# led_analog_watch_mvmt_v1_2.net
KiCad netlist of a schematic drawn in EAGLE
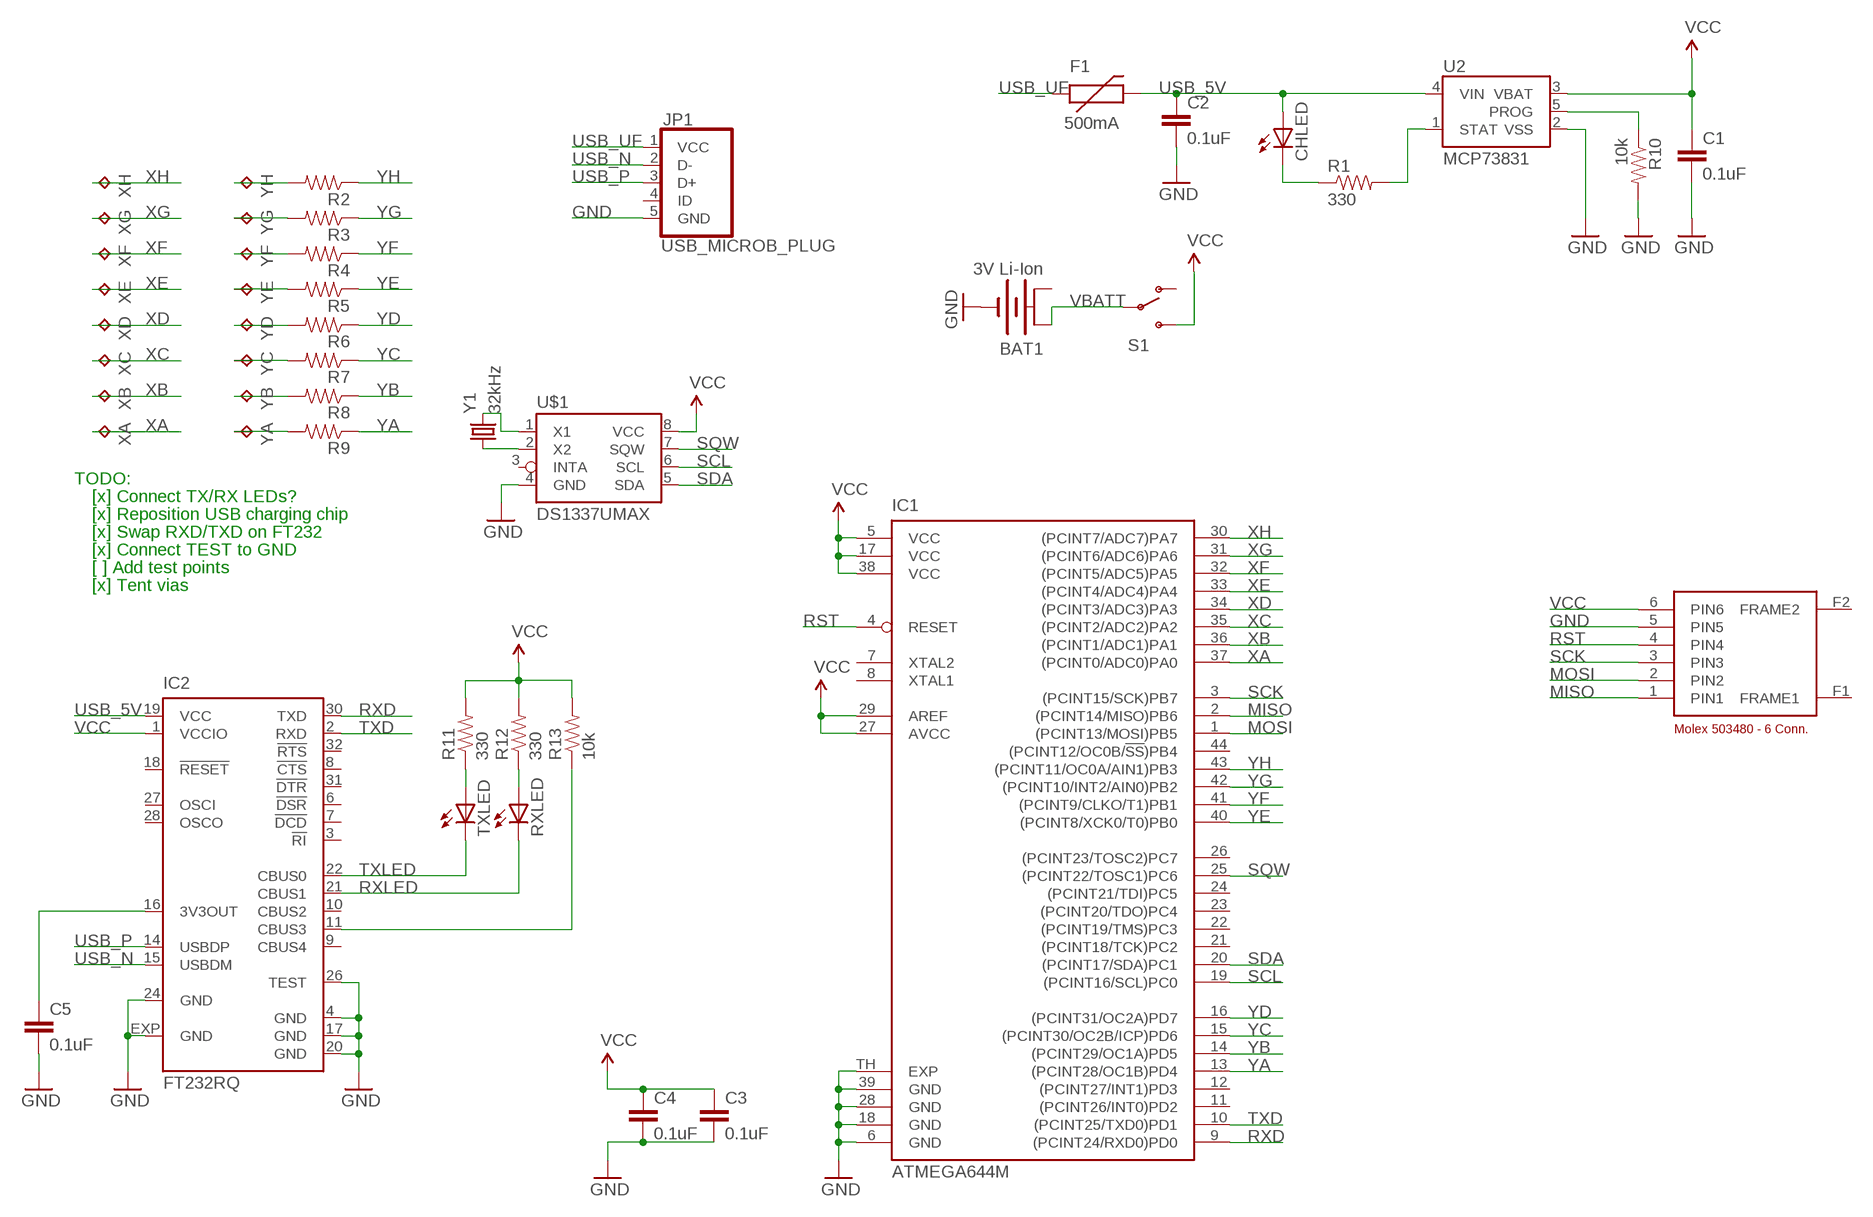
[diagram p0: schematic, sheet 1]

(export (version "E")
  (design (tool "Eeschema 10.0.6"))
  (components
    (comp (ref "BAT1")
      (value "3V Li-Ion")
      (footprint "eagle-import:BATTCON_245MM_PTH")
      (libsource (lib "eagle-import") (part "BATTERY245PTH"))
    )
    (comp (ref "C1")
      (value "0.1uF")
      (footprint "eagle-import:0603-CAP")
      (libsource (lib "eagle-import") (part "CAP-0603"))
    )
    (comp (ref "C2")
      (value "0.1uF")
      (footprint "eagle-import:0603-CAP")
      (libsource (lib "eagle-import") (part "CAP-0603"))
    )
    (comp (ref "C3")
      (value "0.1uF")
      (footprint "eagle-import:0603-CAP")
      (libsource (lib "eagle-import") (part "CAP-0603"))
    )
    (comp (ref "C4")
      (value "0.1uF")
      (footprint "eagle-import:0603-CAP")
      (libsource (lib "eagle-import") (part "CAP-0603"))
    )
    (comp (ref "C5")
      (value "0.1uF")
      (footprint "eagle-import:0603-CAP")
      (libsource (lib "eagle-import") (part "CAP-0603"))
    )
    (comp (ref "CHLED")
      (value "LED-0402")
      (footprint "eagle-import:0402")
      (libsource (lib "eagle-import") (part "LED-0402"))
    )
    (comp (ref "F1")
      (value "500mA")
      (footprint "eagle-import:0603")
      (libsource (lib "eagle-import") (part "PTC0603"))
    )
    (comp (ref "IC1")
      (value "ATMEGA644M")
      (footprint "eagle-import:MLF44-TH")
      (fields (field (name "MPN") "ATMEGA644P-20MU"))
      (libsource (lib "eagle-import") (part "ATMEGA644M"))
    )
    (comp (ref "IC2")
      (value "FT232RQ")
      (footprint "eagle-import:QFN32")
      (libsource (lib "eagle-import") (part "FT232RQ"))
    )
    (comp (ref "JP1")
      (value "USB_MICROB_PLUG")
      (footprint "eagle-import:USB_MICRO_B_TYCO")
      (libsource (lib "eagle-import") (part "USB_MICROB_PLUG"))
    )
    (comp (ref "R1")
      (value "330")
      (footprint "eagle-import:0603")
      (libsource (lib "eagle-import") (part "RESISTOR-0603"))
    )
    (comp (ref "R2")
      (value "RESISTOR-0603")
      (footprint "eagle-import:0603")
      (libsource (lib "eagle-import") (part "RESISTOR-0603"))
    )
    (comp (ref "R3")
      (value "RESISTOR-0603")
      (footprint "eagle-import:0603")
      (libsource (lib "eagle-import") (part "RESISTOR-0603"))
    )
    (comp (ref "R4")
      (value "RESISTOR-0603")
      (footprint "eagle-import:0603")
      (libsource (lib "eagle-import") (part "RESISTOR-0603"))
    )
    (comp (ref "R5")
      (value "RESISTOR-0603")
      (footprint "eagle-import:0603")
      (libsource (lib "eagle-import") (part "RESISTOR-0603"))
    )
    (comp (ref "R6")
      (value "RESISTOR-0603")
      (footprint "eagle-import:0603")
      (libsource (lib "eagle-import") (part "RESISTOR-0603"))
    )
    (comp (ref "R7")
      (value "RESISTOR-0603")
      (footprint "eagle-import:0603")
      (libsource (lib "eagle-import") (part "RESISTOR-0603"))
    )
    (comp (ref "R8")
      (value "RESISTOR-0603")
      (footprint "eagle-import:0603")
      (libsource (lib "eagle-import") (part "RESISTOR-0603"))
    )
    (comp (ref "R9")
      (value "RESISTOR-0603")
      (footprint "eagle-import:0603")
      (libsource (lib "eagle-import") (part "RESISTOR-0603"))
    )
    (comp (ref "R10")
      (value "10k")
      (footprint "eagle-import:0603")
      (libsource (lib "eagle-import") (part "RESISTOR-0603"))
    )
    (comp (ref "R11")
      (value "330")
      (footprint "eagle-import:0603")
      (libsource (lib "eagle-import") (part "RESISTOR-0603"))
    )
    (comp (ref "R12")
      (value "330")
      (footprint "eagle-import:0603")
      (libsource (lib "eagle-import") (part "RESISTOR-0603"))
    )
    (comp (ref "R13")
      (value "10k")
      (footprint "eagle-import:0603")
      (libsource (lib "eagle-import") (part "RESISTOR-0603"))
    )
    (comp (ref "RXLED")
      (value "LED-0402")
      (footprint "eagle-import:0402")
      (libsource (lib "eagle-import") (part "LED-0402"))
    )
    (comp (ref "S1")
      (value "SWITCH-SPSTMA12R")
      (footprint "eagle-import:SWITCH-MA12R")
      (libsource (lib "eagle-import") (part "SWITCH-SPSTMA12R"))
    )
    (comp (ref "TXLED")
      (value "LED-0402")
      (footprint "eagle-import:0402")
      (libsource (lib "eagle-import") (part "LED-0402"))
    )
    (comp (ref "U$1")
      (value "DS1337UMAX")
      (footprint "eagle-import:UMAX8")
      (libsource (lib "eagle-import") (part "DS1337UMAX"))
    )
    (comp (ref "U$2")
      (value "MOLEX_503480")
      (footprint "eagle-import:MOLEX_503480")
      (libsource (lib "eagle-import") (part "MOLEX_503480"))
    )
    (comp (ref "U2")
      (value "MCP73831")
      (footprint "eagle-import:SOT23-5")
      (libsource (lib "eagle-import") (part "MCP73831"))
    )
    (comp (ref "XA")
      (value "TPTP20R")
      (footprint "eagle-import:TP20R")
      (libsource (lib "eagle-import") (part "TPTP20R"))
    )
    (comp (ref "XB")
      (value "TPTP20R")
      (footprint "eagle-import:TP20R")
      (libsource (lib "eagle-import") (part "TPTP20R"))
    )
    (comp (ref "XC")
      (value "TPTP20R")
      (footprint "eagle-import:TP20R")
      (libsource (lib "eagle-import") (part "TPTP20R"))
    )
    (comp (ref "XD")
      (value "TPTP20R")
      (footprint "eagle-import:TP20R")
      (libsource (lib "eagle-import") (part "TPTP20R"))
    )
    (comp (ref "XE")
      (value "TPTP20R")
      (footprint "eagle-import:TP20R")
      (libsource (lib "eagle-import") (part "TPTP20R"))
    )
    (comp (ref "XF")
      (value "TPTP20R")
      (footprint "eagle-import:TP20R")
      (libsource (lib "eagle-import") (part "TPTP20R"))
    )
    (comp (ref "XG")
      (value "TPTP20R")
      (footprint "eagle-import:TP20R")
      (libsource (lib "eagle-import") (part "TPTP20R"))
    )
    (comp (ref "XH")
      (value "TPTP20R")
      (footprint "eagle-import:TP20R")
      (libsource (lib "eagle-import") (part "TPTP20R"))
    )
    (comp (ref "Y1")
      (value "32kHz")
      (footprint "eagle-import:CRYSTAL-ABS10-SMD")
      (libsource (lib "eagle-import") (part "CRYSTALABS10"))
    )
    (comp (ref "YA")
      (value "TPTP20R")
      (footprint "eagle-import:TP20R")
      (libsource (lib "eagle-import") (part "TPTP20R"))
    )
    (comp (ref "YB")
      (value "TPTP20R")
      (footprint "eagle-import:TP20R")
      (libsource (lib "eagle-import") (part "TPTP20R"))
    )
    (comp (ref "YC")
      (value "TPTP20R")
      (footprint "eagle-import:TP20R")
      (libsource (lib "eagle-import") (part "TPTP20R"))
    )
    (comp (ref "YD")
      (value "TPTP20R")
      (footprint "eagle-import:TP20R")
      (libsource (lib "eagle-import") (part "TPTP20R"))
    )
    (comp (ref "YE")
      (value "TPTP20R")
      (footprint "eagle-import:TP20R")
      (libsource (lib "eagle-import") (part "TPTP20R"))
    )
    (comp (ref "YF")
      (value "TPTP20R")
      (footprint "eagle-import:TP20R")
      (libsource (lib "eagle-import") (part "TPTP20R"))
    )
    (comp (ref "YG")
      (value "TPTP20R")
      (footprint "eagle-import:TP20R")
      (libsource (lib "eagle-import") (part "TPTP20R"))
    )
    (comp (ref "YH")
      (value "TPTP20R")
      (footprint "eagle-import:TP20R")
      (libsource (lib "eagle-import") (part "TPTP20R"))
    )
  )
  (nets
    (net (code "1") (name "/+B") (class "Default")
      (node (ref "BAT1") (pin "1") (pinfunction "+B_1") (pintype "power_in"))
    )
    (net (code "2") (name "/MISO") (class "Default")
      (node (ref "IC1") (pin "2") (pinfunction "(PCINT14/MISO)PB6_2") (pintype "bidirectional"))
      (node (ref "U$2") (pin "1") (pinfunction "PIN1_1") (pintype "bidirectional"))
    )
    (net (code "3") (name "/MOSI") (class "Default")
      (node (ref "IC1") (pin "1") (pinfunction "(PCINT13/MOSI)PB5_1") (pintype "bidirectional"))
      (node (ref "U$2") (pin "2") (pinfunction "PIN2_2") (pintype "bidirectional"))
    )
    (net (code "4") (name "/RST") (class "Default")
      (node (ref "IC1") (pin "4") (pinfunction "RESET_4") (pintype "input"))
      (node (ref "U$2") (pin "4") (pinfunction "PIN4_4") (pintype "bidirectional"))
    )
    (net (code "5") (name "/RXD") (class "Default")
      (node (ref "IC1") (pin "9") (pinfunction "(PCINT24/RXD0)PD0_9") (pintype "bidirectional"))
      (node (ref "IC2") (pin "30") (pinfunction "TXD_30") (pintype "output"))
    )
    (net (code "6") (name "/RXLED") (class "Default")
      (node (ref "IC2") (pin "21") (pinfunction "CBUS1_21") (pintype "bidirectional"))
      (node (ref "RXLED") (pin "2") (pinfunction "C_2") (pintype "passive"))
    )
    (net (code "7") (name "/SCK") (class "Default")
      (node (ref "IC1") (pin "3") (pinfunction "(PCINT15/SCK)PB7_3") (pintype "bidirectional"))
      (node (ref "U$2") (pin "3") (pinfunction "PIN3_3") (pintype "bidirectional"))
    )
    (net (code "8") (name "/SCL") (class "Default")
      (node (ref "IC1") (pin "19") (pinfunction "(PCINT16/SCL)PC0_19") (pintype "output"))
      (node (ref "U$1") (pin "6") (pinfunction "SCL_6") (pintype "bidirectional"))
    )
    (net (code "9") (name "/SDA") (class "Default")
      (node (ref "IC1") (pin "20") (pinfunction "(PCINT17/SDA)PC1_20") (pintype "output"))
      (node (ref "U$1") (pin "5") (pinfunction "SDA_5") (pintype "bidirectional"))
    )
    (net (code "10") (name "/SQW") (class "Default")
      (node (ref "IC1") (pin "25") (pinfunction "(PCINT22/TOSC1)PC6_25") (pintype "output"))
      (node (ref "U$1") (pin "7") (pinfunction "SQW_7") (pintype "bidirectional"))
    )
    (net (code "11") (name "/TXD") (class "Default")
      (node (ref "IC1") (pin "10") (pinfunction "(PCINT25/TXD0)PD1_10") (pintype "bidirectional"))
      (node (ref "IC2") (pin "2") (pinfunction "RXD_2") (pintype "input"))
    )
    (net (code "12") (name "/TXLED") (class "Default")
      (node (ref "IC2") (pin "22") (pinfunction "CBUS0_22") (pintype "bidirectional"))
      (node (ref "TXLED") (pin "2") (pinfunction "C_2") (pintype "passive"))
    )
    (net (code "13") (name "/USB_5V") (class "Default")
      (node (ref "C2") (pin "1") (pinfunction "1_1") (pintype "passive"))
      (node (ref "CHLED") (pin "1") (pinfunction "A_1") (pintype "passive"))
      (node (ref "F1") (pin "2") (pinfunction "2_2") (pintype "bidirectional"))
      (node (ref "IC2") (pin "19") (pinfunction "VCC_19") (pintype "power_in"))
      (node (ref "U2") (pin "4") (pinfunction "VIN_4") (pintype "power_in"))
    )
    (net (code "14") (name "/USB_N") (class "Default")
      (node (ref "IC2") (pin "15") (pinfunction "USBDM_15") (pintype "bidirectional"))
      (node (ref "JP1") (pin "2") (pinfunction "D-_2") (pintype "bidirectional"))
    )
    (net (code "15") (name "/USB_P") (class "Default")
      (node (ref "IC2") (pin "14") (pinfunction "USBDP_14") (pintype "bidirectional"))
      (node (ref "JP1") (pin "3") (pinfunction "D+_3") (pintype "bidirectional"))
    )
    (net (code "16") (name "/USB_UF") (class "Default")
      (node (ref "F1") (pin "1") (pinfunction "1_1") (pintype "bidirectional"))
      (node (ref "JP1") (pin "1") (pinfunction "VCC_1") (pintype "bidirectional"))
    )
    (net (code "17") (name "/VBATT") (class "Default")
      (node (ref "BAT1") (pin "3") (pinfunction "+A_3") (pintype "power_in"))
      (node (ref "S1") (pin "2") (pinfunction "P_2") (pintype "passive"))
    )
    (net (code "18") (name "/XA") (class "Default")
      (node (ref "IC1") (pin "37") (pinfunction "(PCINT0/ADC0)PA0_37") (pintype "bidirectional"))
      (node (ref "XA") (pin "TP") (pinfunction "TP_TP") (pintype "input"))
    )
    (net (code "19") (name "/XB") (class "Default")
      (node (ref "IC1") (pin "36") (pinfunction "(PCINT1/ADC1)PA1_36") (pintype "bidirectional"))
      (node (ref "XB") (pin "TP") (pinfunction "TP_TP") (pintype "input"))
    )
    (net (code "20") (name "/XC") (class "Default")
      (node (ref "IC1") (pin "35") (pinfunction "(PCINT2/ADC2)PA2_35") (pintype "bidirectional"))
      (node (ref "XC") (pin "TP") (pinfunction "TP_TP") (pintype "input"))
    )
    (net (code "21") (name "/XD") (class "Default")
      (node (ref "IC1") (pin "34") (pinfunction "(PCINT3/ADC3)PA3_34") (pintype "bidirectional"))
      (node (ref "XD") (pin "TP") (pinfunction "TP_TP") (pintype "input"))
    )
    (net (code "22") (name "/XE") (class "Default")
      (node (ref "IC1") (pin "33") (pinfunction "(PCINT4/ADC4)PA4_33") (pintype "bidirectional"))
      (node (ref "XE") (pin "TP") (pinfunction "TP_TP") (pintype "input"))
    )
    (net (code "23") (name "/XF") (class "Default")
      (node (ref "IC1") (pin "32") (pinfunction "(PCINT5/ADC5)PA5_32") (pintype "bidirectional"))
      (node (ref "XF") (pin "TP") (pinfunction "TP_TP") (pintype "input"))
    )
    (net (code "24") (name "/XG") (class "Default")
      (node (ref "IC1") (pin "31") (pinfunction "(PCINT6/ADC6)PA6_31") (pintype "bidirectional"))
      (node (ref "XG") (pin "TP") (pinfunction "TP_TP") (pintype "input"))
    )
    (net (code "25") (name "/XH") (class "Default")
      (node (ref "IC1") (pin "30") (pinfunction "(PCINT7/ADC7)PA7_30") (pintype "bidirectional"))
      (node (ref "XH") (pin "TP") (pinfunction "TP_TP") (pintype "input"))
    )
    (net (code "26") (name "/YA") (class "Default")
      (node (ref "IC1") (pin "13") (pinfunction "(PCINT28/OC1B)PD4_13") (pintype "bidirectional"))
      (node (ref "R9") (pin "1") (pinfunction "1_1") (pintype "passive"))
    )
    (net (code "27") (name "/YB") (class "Default")
      (node (ref "IC1") (pin "14") (pinfunction "(PCINT29/OC1A)PD5_14") (pintype "bidirectional"))
      (node (ref "R8") (pin "1") (pinfunction "1_1") (pintype "passive"))
    )
    (net (code "28") (name "/YC") (class "Default")
      (node (ref "IC1") (pin "15") (pinfunction "(PCINT30/OC2B/ICP)PD6_15") (pintype "bidirectional"))
      (node (ref "R7") (pin "1") (pinfunction "1_1") (pintype "passive"))
    )
    (net (code "29") (name "/YD") (class "Default")
      (node (ref "IC1") (pin "16") (pinfunction "(PCINT31/OC2A)PD7_16") (pintype "bidirectional"))
      (node (ref "R6") (pin "1") (pinfunction "1_1") (pintype "passive"))
    )
    (net (code "30") (name "/YE") (class "Default")
      (node (ref "IC1") (pin "40") (pinfunction "(PCINT8/XCK0/T0)PB0_40") (pintype "bidirectional"))
      (node (ref "R5") (pin "1") (pinfunction "1_1") (pintype "passive"))
    )
    (net (code "31") (name "/YF") (class "Default")
      (node (ref "IC1") (pin "41") (pinfunction "(PCINT9/CLKO/T1)PB1_41") (pintype "bidirectional"))
      (node (ref "R4") (pin "1") (pinfunction "1_1") (pintype "passive"))
    )
    (net (code "32") (name "/YG") (class "Default")
      (node (ref "IC1") (pin "42") (pinfunction "(PCINT10/INT2/AIN0)PB2_42") (pintype "bidirectional"))
      (node (ref "R3") (pin "1") (pinfunction "1_1") (pintype "passive"))
    )
    (net (code "33") (name "/YH") (class "Default")
      (node (ref "IC1") (pin "43") (pinfunction "(PCINT11/OC0A/AIN1)PB3_43") (pintype "bidirectional"))
      (node (ref "R2") (pin "1") (pinfunction "1_1") (pintype "passive"))
    )
    (net (code "34") (name "GND") (class "Default")
      (node (ref "BAT1") (pin "2") (pinfunction "-_2") (pintype "power_in"))
      (node (ref "C1") (pin "2") (pinfunction "2_2") (pintype "passive"))
      (node (ref "C2") (pin "2") (pinfunction "2_2") (pintype "passive"))
      (node (ref "C3") (pin "2") (pinfunction "2_2") (pintype "passive"))
      (node (ref "C4") (pin "2") (pinfunction "2_2") (pintype "passive"))
      (node (ref "C5") (pin "2") (pinfunction "2_2") (pintype "passive"))
      (node (ref "IC1") (pin "18") (pinfunction "GND_18") (pintype "power_in"))
      (node (ref "IC1") (pin "28") (pinfunction "GND_28") (pintype "power_in"))
      (node (ref "IC1") (pin "39") (pinfunction "GND_39") (pintype "power_in"))
      (node (ref "IC1") (pin "6") (pinfunction "GND_6") (pintype "power_in"))
      (node (ref "IC1") (pin "TH") (pinfunction "EXP_TH") (pintype "power_in"))
      (node (ref "IC2") (pin "17") (pinfunction "GND_17") (pintype "power_in"))
      (node (ref "IC2") (pin "20") (pinfunction "GND_20") (pintype "power_in"))
      (node (ref "IC2") (pin "24") (pinfunction "GND_24") (pintype "power_in"))
      (node (ref "IC2") (pin "26") (pinfunction "TEST_26") (pintype "input"))
      (node (ref "IC2") (pin "4") (pinfunction "GND_4") (pintype "power_in"))
      (node (ref "IC2") (pin "EXP") (pinfunction "GND_EXP") (pintype "power_in"))
      (node (ref "JP1") (pin "5") (pinfunction "GND_5") (pintype "bidirectional"))
      (node (ref "R10") (pin "2") (pinfunction "2_2") (pintype "passive"))
      (node (ref "U$1") (pin "4") (pinfunction "GND_4") (pintype "bidirectional"))
      (node (ref "U$2") (pin "5") (pinfunction "PIN5_5") (pintype "bidirectional"))
      (node (ref "U2") (pin "2") (pinfunction "VSS_2") (pintype "power_in"))
    )
    (net (code "35") (name "Net-(CHLED-C)") (class "Default")
      (node (ref "CHLED") (pin "2") (pinfunction "C_2") (pintype "passive"))
      (node (ref "R1") (pin "1") (pinfunction "1_1") (pintype "passive"))
    )
    (net (code "36") (name "Net-(IC2-3V3OUT)") (class "Default")
      (node (ref "C5") (pin "1") (pinfunction "1_1") (pintype "passive"))
      (node (ref "IC2") (pin "16") (pinfunction "3V3OUT_16") (pintype "output"))
    )
    (net (code "37") (name "Net-(IC2-CBUS3)") (class "Default")
      (node (ref "IC2") (pin "11") (pinfunction "CBUS3_11") (pintype "bidirectional"))
      (node (ref "R13") (pin "1") (pinfunction "1_1") (pintype "passive"))
    )
    (net (code "38") (name "Net-(R2-Pad2)") (class "Default")
      (node (ref "R2") (pin "2") (pinfunction "2_2") (pintype "passive"))
      (node (ref "YH") (pin "TP") (pinfunction "TP_TP") (pintype "input"))
    )
    (net (code "39") (name "Net-(R3-Pad2)") (class "Default")
      (node (ref "R3") (pin "2") (pinfunction "2_2") (pintype "passive"))
      (node (ref "YG") (pin "TP") (pinfunction "TP_TP") (pintype "input"))
    )
    (net (code "40") (name "Net-(R4-Pad2)") (class "Default")
      (node (ref "R4") (pin "2") (pinfunction "2_2") (pintype "passive"))
      (node (ref "YF") (pin "TP") (pinfunction "TP_TP") (pintype "input"))
    )
    (net (code "41") (name "Net-(R5-Pad2)") (class "Default")
      (node (ref "R5") (pin "2") (pinfunction "2_2") (pintype "passive"))
      (node (ref "YE") (pin "TP") (pinfunction "TP_TP") (pintype "input"))
    )
    (net (code "42") (name "Net-(R6-Pad2)") (class "Default")
      (node (ref "R6") (pin "2") (pinfunction "2_2") (pintype "passive"))
      (node (ref "YD") (pin "TP") (pinfunction "TP_TP") (pintype "input"))
    )
    (net (code "43") (name "Net-(R7-Pad2)") (class "Default")
      (node (ref "R7") (pin "2") (pinfunction "2_2") (pintype "passive"))
      (node (ref "YC") (pin "TP") (pinfunction "TP_TP") (pintype "input"))
    )
    (net (code "44") (name "Net-(R8-Pad2)") (class "Default")
      (node (ref "R8") (pin "2") (pinfunction "2_2") (pintype "passive"))
      (node (ref "YB") (pin "TP") (pinfunction "TP_TP") (pintype "input"))
    )
    (net (code "45") (name "Net-(R9-Pad2)") (class "Default")
      (node (ref "R9") (pin "2") (pinfunction "2_2") (pintype "passive"))
      (node (ref "YA") (pin "TP") (pinfunction "TP_TP") (pintype "input"))
    )
    (net (code "46") (name "Net-(RXLED-A)") (class "Default")
      (node (ref "R12") (pin "1") (pinfunction "1_1") (pintype "passive"))
      (node (ref "RXLED") (pin "1") (pinfunction "A_1") (pintype "passive"))
    )
    (net (code "47") (name "Net-(TXLED-A)") (class "Default")
      (node (ref "R11") (pin "1") (pinfunction "1_1") (pintype "passive"))
      (node (ref "TXLED") (pin "1") (pinfunction "A_1") (pintype "passive"))
    )
    (net (code "48") (name "Net-(U$1-X1)") (class "Default")
      (node (ref "U$1") (pin "1") (pinfunction "X1_1") (pintype "bidirectional"))
      (node (ref "Y1") (pin "X2") (pinfunction "2_X2") (pintype "passive"))
    )
    (net (code "49") (name "Net-(U$1-X2)") (class "Default")
      (node (ref "U$1") (pin "2") (pinfunction "X2_2") (pintype "bidirectional"))
      (node (ref "Y1") (pin "X1") (pinfunction "1_X1") (pintype "passive"))
    )
    (net (code "50") (name "Net-(U2-PROG)") (class "Default")
      (node (ref "R10") (pin "1") (pinfunction "1_1") (pintype "passive"))
      (node (ref "U2") (pin "5") (pinfunction "PROG_5") (pintype "input"))
    )
    (net (code "51") (name "Net-(U2-STAT)") (class "Default")
      (node (ref "R1") (pin "2") (pinfunction "2_2") (pintype "passive"))
      (node (ref "U2") (pin "1") (pinfunction "STAT_1") (pintype "output"))
    )
    (net (code "52") (name "VCC") (class "Default")
      (node (ref "C1") (pin "1") (pinfunction "1_1") (pintype "passive"))
      (node (ref "C3") (pin "1") (pinfunction "1_1") (pintype "passive"))
      (node (ref "C4") (pin "1") (pinfunction "1_1") (pintype "passive"))
      (node (ref "IC1") (pin "17") (pinfunction "VCC_17") (pintype "power_in"))
      (node (ref "IC1") (pin "27") (pinfunction "AVCC_27") (pintype "power_in"))
      (node (ref "IC1") (pin "29") (pinfunction "AREF_29") (pintype "passive"))
      (node (ref "IC1") (pin "38") (pinfunction "VCC_38") (pintype "power_in"))
      (node (ref "IC1") (pin "5") (pinfunction "VCC_5") (pintype "power_in"))
      (node (ref "IC2") (pin "1") (pinfunction "VCCIO_1") (pintype "power_in"))
      (node (ref "R11") (pin "2") (pinfunction "2_2") (pintype "passive"))
      (node (ref "R12") (pin "2") (pinfunction "2_2") (pintype "passive"))
      (node (ref "R13") (pin "2") (pinfunction "2_2") (pintype "passive"))
      (node (ref "S1") (pin "3") (pinfunction "S_3") (pintype "passive"))
      (node (ref "U$1") (pin "8") (pinfunction "VCC_8") (pintype "bidirectional"))
      (node (ref "U$2") (pin "6") (pinfunction "PIN6_6") (pintype "bidirectional"))
      (node (ref "U2") (pin "3") (pinfunction "VBAT_3") (pintype "power_in"))
    )
    (net (code "53") (name "unconnected-(IC1-(PCINT12{slash}OC0B{slash}~{SS})PB4-Pad44)") (class "Default")
      (node (ref "IC1") (pin "44") (pinfunction "(PCINT12/OC0B/~{SS})PB4_44") (pintype "bidirectional"))
    )
    (net (code "54") (name "unconnected-(IC1-(PCINT18{slash}TCK)PC2-Pad21)") (class "Default")
      (node (ref "IC1") (pin "21") (pinfunction "(PCINT18/TCK)PC2_21") (pintype "output"))
    )
    (net (code "55") (name "unconnected-(IC1-(PCINT19{slash}TMS)PC3-Pad22)") (class "Default")
      (node (ref "IC1") (pin "22") (pinfunction "(PCINT19/TMS)PC3_22") (pintype "output"))
    )
    (net (code "56") (name "unconnected-(IC1-(PCINT20{slash}TDO)PC4-Pad23)") (class "Default")
      (node (ref "IC1") (pin "23") (pinfunction "(PCINT20/TDO)PC4_23") (pintype "output"))
    )
    (net (code "57") (name "unconnected-(IC1-(PCINT21{slash}TDI)PC5-Pad24)") (class "Default")
      (node (ref "IC1") (pin "24") (pinfunction "(PCINT21/TDI)PC5_24") (pintype "output"))
    )
    (net (code "58") (name "unconnected-(IC1-(PCINT23{slash}TOSC2)PC7-Pad26)") (class "Default")
      (node (ref "IC1") (pin "26") (pinfunction "(PCINT23/TOSC2)PC7_26") (pintype "output"))
    )
    (net (code "59") (name "unconnected-(IC1-(PCINT26{slash}INT0)PD2-Pad11)") (class "Default")
      (node (ref "IC1") (pin "11") (pinfunction "(PCINT26/INT0)PD2_11") (pintype "bidirectional"))
    )
    (net (code "60") (name "unconnected-(IC1-(PCINT27{slash}INT1)PD3-Pad12)") (class "Default")
      (node (ref "IC1") (pin "12") (pinfunction "(PCINT27/INT1)PD3_12") (pintype "bidirectional"))
    )
    (net (code "61") (name "unconnected-(IC1-XTAL1-Pad8)") (class "Default")
      (node (ref "IC1") (pin "8") (pinfunction "XTAL1_8") (pintype "bidirectional"))
    )
    (net (code "62") (name "unconnected-(IC1-XTAL2-Pad7)") (class "Default")
      (node (ref "IC1") (pin "7") (pinfunction "XTAL2_7") (pintype "bidirectional"))
    )
    (net (code "63") (name "unconnected-(IC2-CBUS2-Pad10)") (class "Default")
      (node (ref "IC2") (pin "10") (pinfunction "CBUS2_10") (pintype "bidirectional"))
    )
    (net (code "64") (name "unconnected-(IC2-CBUS4-Pad9)") (class "Default")
      (node (ref "IC2") (pin "9") (pinfunction "CBUS4_9") (pintype "bidirectional"))
    )
    (net (code "65") (name "unconnected-(IC2-OSCI-Pad27)") (class "Default")
      (node (ref "IC2") (pin "27") (pinfunction "OSCI_27") (pintype "input"))
    )
    (net (code "66") (name "unconnected-(IC2-OSCO-Pad28)") (class "Default")
      (node (ref "IC2") (pin "28") (pinfunction "OSCO_28") (pintype "output"))
    )
    (net (code "67") (name "unconnected-(IC2-~{CTS}-Pad8)") (class "Default")
      (node (ref "IC2") (pin "8") (pinfunction "~{CTS}_8") (pintype "input"))
    )
    (net (code "68") (name "unconnected-(IC2-~{DCD}-Pad7)") (class "Default")
      (node (ref "IC2") (pin "7") (pinfunction "~{DCD}_7") (pintype "input"))
    )
    (net (code "69") (name "unconnected-(IC2-~{DSR}-Pad6)") (class "Default")
      (node (ref "IC2") (pin "6") (pinfunction "~{DSR}_6") (pintype "input"))
    )
    (net (code "70") (name "unconnected-(IC2-~{DTR}-Pad31)") (class "Default")
      (node (ref "IC2") (pin "31") (pinfunction "~{DTR}_31") (pintype "output"))
    )
    (net (code "71") (name "unconnected-(IC2-~{RESET}-Pad18)") (class "Default")
      (node (ref "IC2") (pin "18") (pinfunction "~{RESET}_18") (pintype "input"))
    )
    (net (code "72") (name "unconnected-(IC2-~{RI}-Pad3)") (class "Default")
      (node (ref "IC2") (pin "3") (pinfunction "~{RI}_3") (pintype "input"))
    )
    (net (code "73") (name "unconnected-(IC2-~{RTS}-Pad32)") (class "Default")
      (node (ref "IC2") (pin "32") (pinfunction "~{RTS}_32") (pintype "output"))
    )
    (net (code "74") (name "unconnected-(JP1-ID-Pad4)") (class "Default")
      (node (ref "JP1") (pin "4") (pinfunction "ID_4") (pintype "bidirectional"))
    )
    (net (code "75") (name "unconnected-(S1-O-Pad1)") (class "Default")
      (node (ref "S1") (pin "1") (pinfunction "O_1") (pintype "passive"))
    )
    (net (code "76") (name "unconnected-(U$1-INTA-Pad3)") (class "Default")
      (node (ref "U$1") (pin "3") (pinfunction "INTA_3") (pintype "bidirectional"))
    )
    (net (code "77") (name "unconnected-(U$2-FRAME1-PadF1)") (class "Default")
      (node (ref "U$2") (pin "F1") (pinfunction "FRAME1_F1") (pintype "bidirectional"))
    )
    (net (code "78") (name "unconnected-(U$2-FRAME2-PadF2)") (class "Default")
      (node (ref "U$2") (pin "F2") (pinfunction "FRAME2_F2") (pintype "bidirectional"))
    )
  )
)
